# demultiplexer.net
KiCad netlist of a schematic drawn in EAGLE
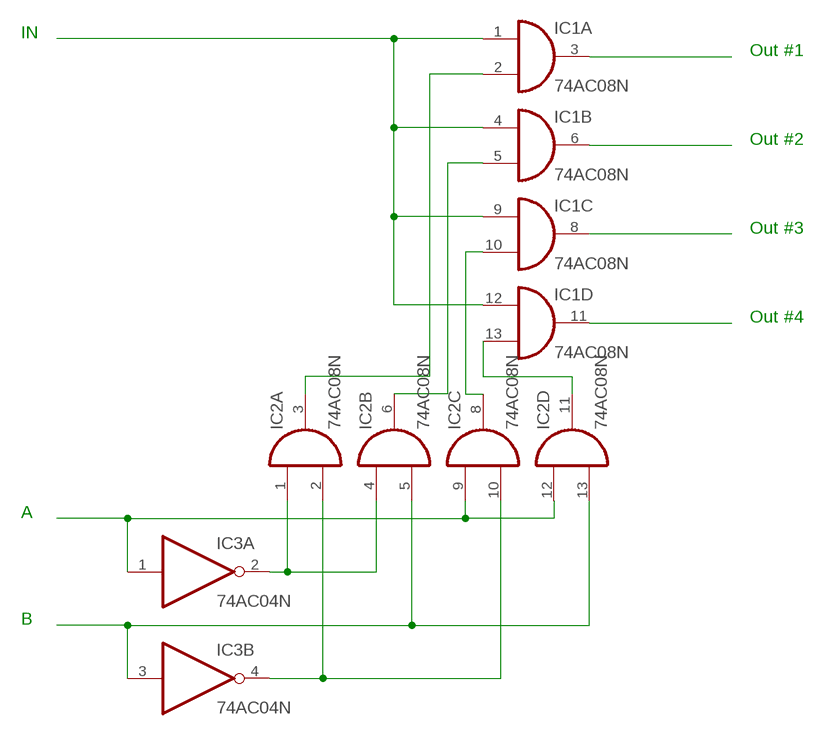
[diagram p0: schematic, sheet 1]

(export (version "E")
  (design (tool "Eeschema 10.0.6"))
  (components
    (comp (ref "IC1")
      (value "74AC08N")
      (footprint "eagle-import:DIL14")
      (libsource (lib "eagle-import") (part "7408NAC"))
    )
    (comp (ref "IC2")
      (value "74AC08N")
      (footprint "eagle-import:DIL14")
      (libsource (lib "eagle-import") (part "7408NAC"))
    )
    (comp (ref "IC3")
      (value "74AC04N")
      (footprint "eagle-import:DIL14")
      (libsource (lib "eagle-import") (part "7404NAC"))
    )
  )
  (nets
    (net (code "1") (name "Net-(IC1A-I0)") (class "Default")
      (node (ref "IC1") (pin "1") (pinfunction "I0_1") (pintype "input"))
      (node (ref "IC1") (pin "12") (pinfunction "I0_12") (pintype "input"))
      (node (ref "IC1") (pin "4") (pinfunction "I0_4") (pintype "input"))
      (node (ref "IC1") (pin "9") (pinfunction "I0_9") (pintype "input"))
    )
    (net (code "2") (name "Net-(IC1A-I1)") (class "Default")
      (node (ref "IC1") (pin "2") (pinfunction "I1_2") (pintype "input"))
      (node (ref "IC2") (pin "3") (pinfunction "O_3") (pintype "output"))
    )
    (net (code "3") (name "Net-(IC1B-I1)") (class "Default")
      (node (ref "IC1") (pin "5") (pinfunction "I1_5") (pintype "input"))
      (node (ref "IC2") (pin "6") (pinfunction "O_6") (pintype "output"))
    )
    (net (code "4") (name "Net-(IC1C-I1)") (class "Default")
      (node (ref "IC1") (pin "10") (pinfunction "I1_10") (pintype "input"))
      (node (ref "IC2") (pin "8") (pinfunction "O_8") (pintype "output"))
    )
    (net (code "5") (name "Net-(IC1D-I1)") (class "Default")
      (node (ref "IC1") (pin "13") (pinfunction "I1_13") (pintype "input"))
      (node (ref "IC2") (pin "11") (pinfunction "O_11") (pintype "output"))
    )
    (net (code "6") (name "Net-(IC2A-I0)") (class "Default")
      (node (ref "IC2") (pin "1") (pinfunction "I0_1") (pintype "input"))
      (node (ref "IC2") (pin "4") (pinfunction "I0_4") (pintype "input"))
      (node (ref "IC3") (pin "2") (pinfunction "O_2") (pintype "output"))
    )
    (net (code "7") (name "Net-(IC2A-I1)") (class "Default")
      (node (ref "IC2") (pin "10") (pinfunction "I1_10") (pintype "input"))
      (node (ref "IC2") (pin "2") (pinfunction "I1_2") (pintype "input"))
      (node (ref "IC3") (pin "4") (pinfunction "O_4") (pintype "output"))
    )
    (net (code "8") (name "Net-(IC2B-I1)") (class "Default")
      (node (ref "IC2") (pin "13") (pinfunction "I1_13") (pintype "input"))
      (node (ref "IC2") (pin "5") (pinfunction "I1_5") (pintype "input"))
      (node (ref "IC3") (pin "3") (pinfunction "I_3") (pintype "input"))
    )
    (net (code "9") (name "Net-(IC2C-I0)") (class "Default")
      (node (ref "IC2") (pin "12") (pinfunction "I0_12") (pintype "input"))
      (node (ref "IC2") (pin "9") (pinfunction "I0_9") (pintype "input"))
      (node (ref "IC3") (pin "1") (pinfunction "I_1") (pintype "input"))
    )
    (net (code "10") (name "unconnected-(IC1A-O-Pad3)") (class "Default")
      (node (ref "IC1") (pin "3") (pinfunction "O_3") (pintype "output"))
    )
    (net (code "11") (name "unconnected-(IC1B-O-Pad6)") (class "Default")
      (node (ref "IC1") (pin "6") (pinfunction "O_6") (pintype "output"))
    )
    (net (code "12") (name "unconnected-(IC1C-O-Pad8)") (class "Default")
      (node (ref "IC1") (pin "8") (pinfunction "O_8") (pintype "output"))
    )
    (net (code "13") (name "unconnected-(IC1D-O-Pad11)") (class "Default")
      (node (ref "IC1") (pin "11") (pinfunction "O_11") (pintype "output"))
    )
  )
)
